# DSO_Trig.net
KiCad netlist of a schematic drawn in Altium Designer
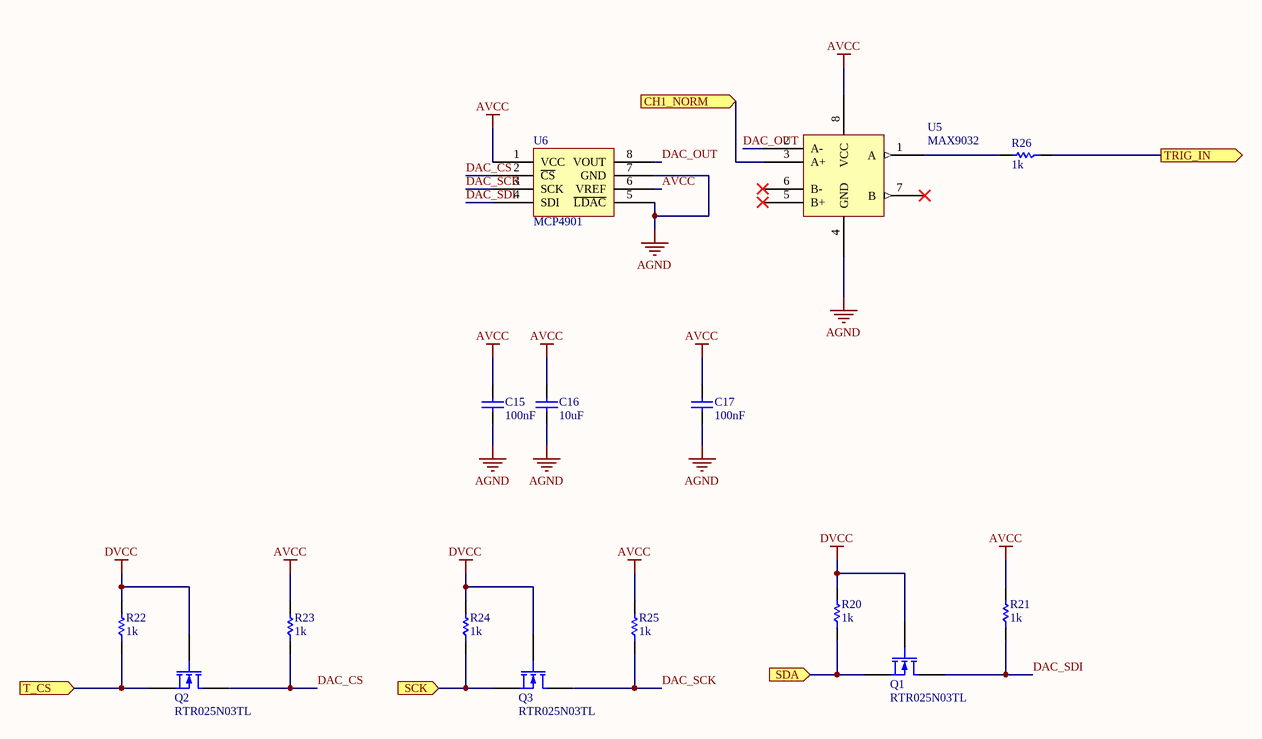
[diagram p0: DSO_Trig.SchDoc]

(export (version "E")
  (design (tool "Eeschema 10.0.6"))
  (components
    (comp (ref "C15")
      (value "100nF")
      (footprint "0805C")
      (description "Capacitor")
      (fields (field (name "REVIEWED BY") "RM - 2018/08/05"))
      (libsource (lib "DSO") (part "C"))
    )
    (comp (ref "C16")
      (value "10uF")
      (footprint "0805C")
      (description "Capacitor")
      (fields (field (name "REVIEWED BY") "RM - 2018/08/05"))
      (libsource (lib "DSO") (part "C"))
    )
    (comp (ref "C17")
      (value "100nF")
      (footprint "0805C")
      (description "Capacitor")
      (fields (field (name "REVIEWED BY") "RM - 2018/08/05"))
      (libsource (lib "DSO") (part "C"))
    )
    (comp (ref "Q1")
      (value "RTR025N03TL")
      (footprint "SOT23")
      (description "N-Channel MOSFET")
      (fields (field (name "PUBLISHER") "Altium Limited"))
      (libsource (lib "RPOT") (part "MOSFET-N"))
    )
    (comp (ref "Q2")
      (value "RTR025N03TL")
      (footprint "SOT23")
      (description "N-Channel MOSFET")
      (fields (field (name "PUBLISHER") "Altium Limited"))
      (libsource (lib "RPOT") (part "MOSFET-N"))
    )
    (comp (ref "Q3")
      (value "RTR025N03TL")
      (footprint "SOT23")
      (description "N-Channel MOSFET")
      (fields (field (name "PUBLISHER") "Altium Limited"))
      (libsource (lib "RPOT") (part "MOSFET-N"))
    )
    (comp (ref "R20")
      (value "1k")
      (footprint "0805")
      (description "Resistor")
      (fields (field (name "REVIEWED BY") "RM - 2018/08/05"))
      (libsource (lib "DSO") (part "R"))
    )
    (comp (ref "R21")
      (value "1k")
      (footprint "0805")
      (description "Resistor")
      (fields (field (name "REVIEWED BY") "RM - 2018/08/05"))
      (libsource (lib "DSO") (part "R"))
    )
    (comp (ref "R22")
      (value "1k")
      (footprint "0805")
      (description "Resistor")
      (fields (field (name "REVIEWED BY") "RM - 2018/08/05"))
      (libsource (lib "DSO") (part "R"))
    )
    (comp (ref "R23")
      (value "1k")
      (footprint "0805")
      (description "Resistor")
      (fields (field (name "REVIEWED BY") "RM - 2018/08/05"))
      (libsource (lib "DSO") (part "R"))
    )
    (comp (ref "R24")
      (value "1k")
      (footprint "0805")
      (description "Resistor")
      (fields (field (name "REVIEWED BY") "RM - 2018/08/05"))
      (libsource (lib "DSO") (part "R"))
    )
    (comp (ref "R25")
      (value "1k")
      (footprint "0805")
      (description "Resistor")
      (fields (field (name "REVIEWED BY") "RM - 2018/08/05"))
      (libsource (lib "DSO") (part "R"))
    )
    (comp (ref "R26")
      (value "1k")
      (footprint "0805")
      (description "Resistor")
      (fields (field (name "REVIEWED BY") "RM - 2018/08/05"))
      (libsource (lib "DSO") (part "R"))
    )
    (comp (ref "U5")
      (value "MAX9032")
      (footprint "SOIC-8")
      (description "Dual Comparator")
      (fields (field (name "REVIEWED BY") "RM - 2018/08/05"))
      (libsource (lib "DSO") (part "MAX9032"))
    )
    (comp (ref "U6")
      (value "MCP4901")
      (footprint "SOIC-8")
      (description "DAC 8bit SPI")
      (fields (field (name "REVIEWED BY") "RM - 2018/08/05"))
      (libsource (lib "DSO") (part "MCP4901"))
    )
  )
  (nets
    (net (code "1") (name "/CH1_NORM") (class "Default")
      (node (ref "U5") (pin "3") (pinfunction "A+_3") (pintype "passive"))
    )
    (net (code "2") (name "/DAC_CS") (class "Default")
      (node (ref "Q2") (pin "3") (pinfunction "3_3") (pintype "passive"))
      (node (ref "R23") (pin "1") (pintype "passive"))
      (node (ref "U6") (pin "2") (pinfunction "~{CS}_2") (pintype "passive"))
    )
    (net (code "3") (name "/DAC_OUT") (class "Default")
      (node (ref "U5") (pin "2") (pinfunction "A-_2") (pintype "passive"))
      (node (ref "U6") (pin "8") (pinfunction "VOUT_8") (pintype "passive"))
    )
    (net (code "4") (name "/DAC_SCK") (class "Default")
      (node (ref "Q3") (pin "3") (pinfunction "3_3") (pintype "passive"))
      (node (ref "R25") (pin "1") (pintype "passive"))
      (node (ref "U6") (pin "3") (pinfunction "SCK_3") (pintype "passive"))
    )
    (net (code "5") (name "/DAC_SDI") (class "Default")
      (node (ref "Q1") (pin "3") (pinfunction "3_3") (pintype "passive"))
      (node (ref "R21") (pin "1") (pintype "passive"))
      (node (ref "U6") (pin "4") (pinfunction "SDI_4") (pintype "passive"))
    )
    (net (code "6") (name "/SCK") (class "Default")
      (node (ref "Q3") (pin "2") (pinfunction "2_2") (pintype "passive"))
      (node (ref "R24") (pin "1") (pintype "passive"))
    )
    (net (code "7") (name "/SDA") (class "Default")
      (node (ref "Q1") (pin "2") (pinfunction "2_2") (pintype "passive"))
      (node (ref "R20") (pin "1") (pintype "passive"))
    )
    (net (code "8") (name "/TRIG_IN") (class "Default") (node (ref "R26") (pin "1") (pintype "passive")))
    (net (code "9") (name "/T_CS") (class "Default")
      (node (ref "Q2") (pin "2") (pinfunction "2_2") (pintype "passive"))
      (node (ref "R22") (pin "1") (pintype "passive"))
    )
    (net (code "10") (name "AGND") (class "Default")
      (node (ref "C15") (pin "2") (pinfunction "2_2") (pintype "passive"))
      (node (ref "C16") (pin "2") (pinfunction "2_2") (pintype "passive"))
      (node (ref "C17") (pin "2") (pinfunction "2_2") (pintype "passive"))
      (node (ref "U5") (pin "4") (pinfunction "GND_4") (pintype "passive"))
      (node (ref "U6") (pin "5") (pinfunction "~{LDAC}_5") (pintype "passive"))
      (node (ref "U6") (pin "7") (pinfunction "GND_7") (pintype "passive"))
    )
    (net (code "11") (name "AVCC") (class "Default")
      (node (ref "C15") (pin "1") (pinfunction "1_1") (pintype "passive"))
      (node (ref "C16") (pin "1") (pinfunction "1_1") (pintype "passive"))
      (node (ref "C17") (pin "1") (pinfunction "1_1") (pintype "passive"))
      (node (ref "R21") (pin "2") (pintype "passive"))
      (node (ref "R23") (pin "2") (pintype "passive"))
      (node (ref "R25") (pin "2") (pintype "passive"))
      (node (ref "U5") (pin "8") (pinfunction "VCC_8") (pintype "passive"))
      (node (ref "U6") (pin "1") (pinfunction "VCC_1") (pintype "passive"))
      (node (ref "U6") (pin "6") (pinfunction "VREF_6") (pintype "passive"))
    )
    (net (code "12") (name "DVCC") (class "Default")
      (node (ref "Q1") (pin "1") (pinfunction "1_1") (pintype "passive"))
      (node (ref "Q2") (pin "1") (pinfunction "1_1") (pintype "passive"))
      (node (ref "Q3") (pin "1") (pinfunction "1_1") (pintype "passive"))
      (node (ref "R20") (pin "2") (pintype "passive"))
      (node (ref "R22") (pin "2") (pintype "passive"))
      (node (ref "R24") (pin "2") (pintype "passive"))
    )
    (net (code "13") (name "Net-(U5-A)") (class "Default")
      (node (ref "R26") (pin "2") (pintype "passive"))
      (node (ref "U5") (pin "1") (pinfunction "A_1") (pintype "output"))
    )
    (net (code "14") (name "unconnected-(U5-B+-Pad5)") (class "Default")
      (node (ref "U5") (pin "5") (pinfunction "B+_5") (pintype "passive+no_connect"))
    )
    (net (code "15") (name "unconnected-(U5-B--Pad6)") (class "Default")
      (node (ref "U5") (pin "6") (pinfunction "B-_6") (pintype "passive+no_connect"))
    )
    (net (code "16") (name "unconnected-(U5-B-Pad7)") (class "Default")
      (node (ref "U5") (pin "7") (pinfunction "B_7") (pintype "output+no_connect"))
    )
  )
)
